# Sheet1.net
KiCad netlist of a schematic drawn in Altium Designer
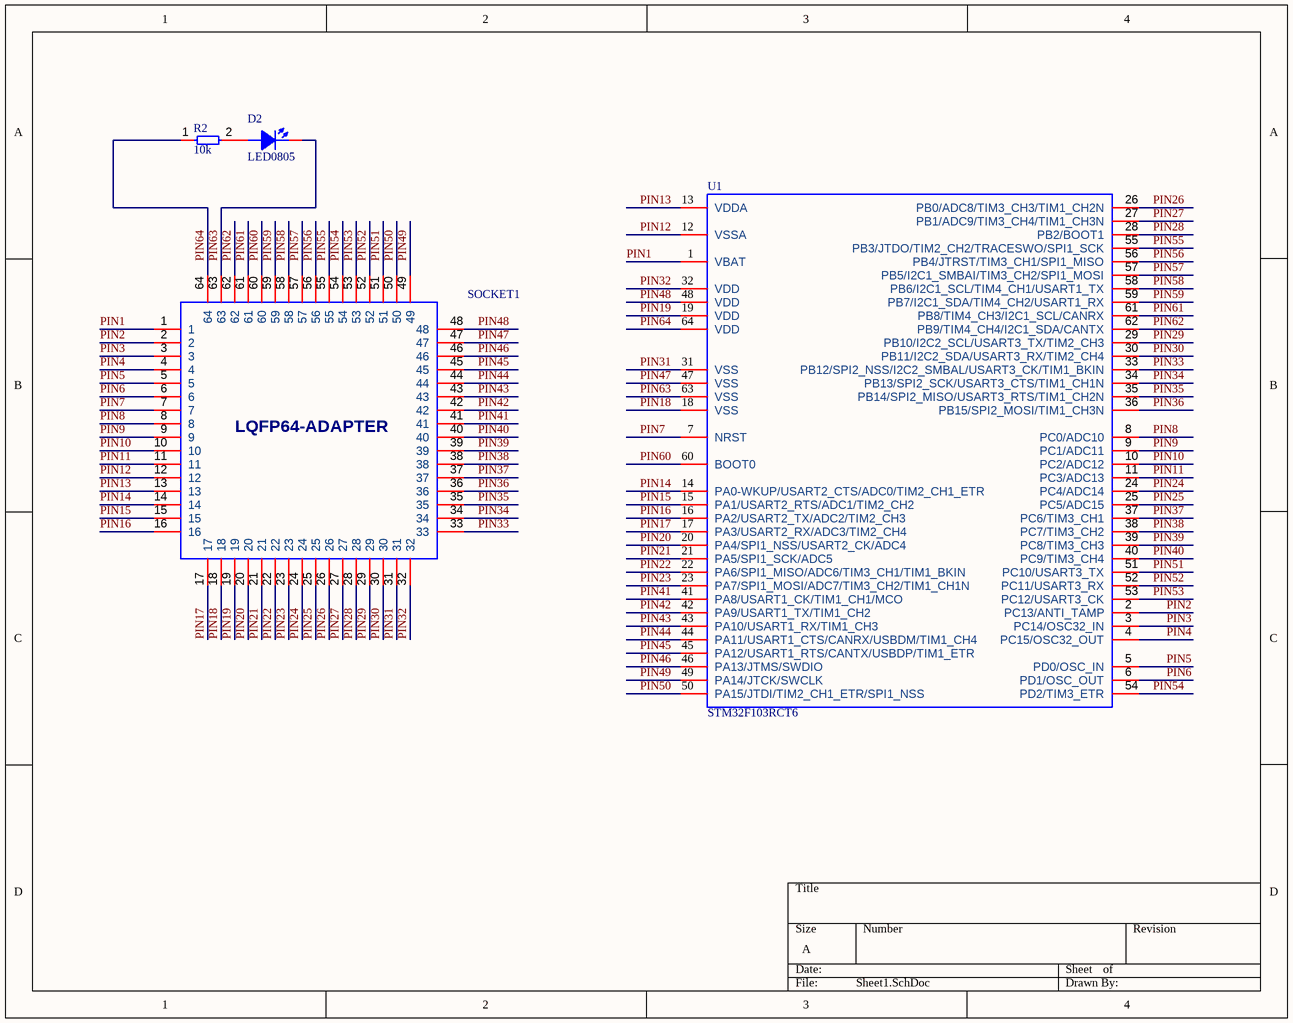
[diagram p0: Sheet1.SchDoc]

(export (version "E")
  (design (tool "Eeschema 10.0.6"))
  (components
    (comp (ref "D2") (value "LED0805") (footprint "L0805RED") (libsource (lib "SMDLibrary") (part "LED0805")))
    (comp (ref "R2") (value "10k") (footprint "R0805") (libsource (lib "SMDLibrary") (part "Resistor SMD")))
    (comp (ref "SOCKET1")
      (value "SOCKET-ADAPTER-OTQ-64-05-03")
      (footprint "SOCKET-ADAPTER-OTQ-64-05-03")
      (libsource (lib "SMDLibrary") (part "SOCKET-ADAPTER-OTQ-64-05-03"))
    )
    (comp (ref "U1")
      (value "STM32F103RCT6")
      (footprint "LQFP064_FPT-64P-M03")
      (description "LQFP64")
      (libsource (lib "SMDLibrary") (part "STM32F103RCT6"))
    )
  )
  (nets
    (net (code "1") (name "/PIN1") (class "Default")
      (node (ref "SOCKET1") (pin "1") (pinfunction "1_1") (pintype "passive"))
      (node (ref "U1") (pin "1") (pinfunction "VBAT_1") (pintype "passive"))
    )
    (net (code "2") (name "/PIN2") (class "Default")
      (node (ref "SOCKET1") (pin "2") (pinfunction "2_2") (pintype "passive"))
      (node (ref "U1") (pin "2") (pinfunction "PC13/ANTI_TAMP_2") (pintype "passive"))
    )
    (net (code "3") (name "/PIN3") (class "Default")
      (node (ref "SOCKET1") (pin "3") (pinfunction "3_3") (pintype "passive"))
      (node (ref "U1") (pin "3") (pinfunction "PC14/OSC32_IN_3") (pintype "passive"))
    )
    (net (code "4") (name "/PIN4") (class "Default")
      (node (ref "SOCKET1") (pin "4") (pinfunction "4_4") (pintype "passive"))
      (node (ref "U1") (pin "4") (pinfunction "PC15/OSC32_OUT_4") (pintype "passive"))
    )
    (net (code "5") (name "/PIN5") (class "Default")
      (node (ref "SOCKET1") (pin "5") (pinfunction "5_5") (pintype "passive"))
      (node (ref "U1") (pin "5") (pinfunction "PD0/OSC_IN_5") (pintype "passive"))
    )
    (net (code "6") (name "/PIN6") (class "Default")
      (node (ref "SOCKET1") (pin "6") (pinfunction "6_6") (pintype "passive"))
      (node (ref "U1") (pin "6") (pinfunction "PD1/OSC_OUT_6") (pintype "passive"))
    )
    (net (code "7") (name "/PIN7") (class "Default")
      (node (ref "SOCKET1") (pin "7") (pinfunction "7_7") (pintype "passive"))
      (node (ref "U1") (pin "7") (pinfunction "NRST_7") (pintype "passive"))
    )
    (net (code "8") (name "/PIN8") (class "Default")
      (node (ref "SOCKET1") (pin "8") (pinfunction "8_8") (pintype "passive"))
      (node (ref "U1") (pin "8") (pinfunction "PC0/ADC10_8") (pintype "passive"))
    )
    (net (code "9") (name "/PIN9") (class "Default")
      (node (ref "SOCKET1") (pin "9") (pinfunction "9_9") (pintype "passive"))
      (node (ref "U1") (pin "9") (pinfunction "PC1/ADC11_9") (pintype "passive"))
    )
    (net (code "10") (name "/PIN10") (class "Default")
      (node (ref "SOCKET1") (pin "10") (pinfunction "10_10") (pintype "passive"))
      (node (ref "U1") (pin "10") (pinfunction "PC2/ADC12_10") (pintype "passive"))
    )
    (net (code "11") (name "/PIN11") (class "Default")
      (node (ref "SOCKET1") (pin "11") (pinfunction "11_11") (pintype "passive"))
      (node (ref "U1") (pin "11") (pinfunction "PC3/ADC13_11") (pintype "passive"))
    )
    (net (code "12") (name "/PIN12") (class "Default")
      (node (ref "SOCKET1") (pin "12") (pinfunction "12_12") (pintype "passive"))
      (node (ref "U1") (pin "12") (pinfunction "VSSA_12") (pintype "passive"))
    )
    (net (code "13") (name "/PIN13") (class "Default")
      (node (ref "SOCKET1") (pin "13") (pinfunction "13_13") (pintype "passive"))
      (node (ref "U1") (pin "13") (pinfunction "VDDA_13") (pintype "passive"))
    )
    (net (code "14") (name "/PIN14") (class "Default")
      (node (ref "SOCKET1") (pin "14") (pinfunction "14_14") (pintype "passive"))
      (node (ref "U1") (pin "14") (pinfunction "PA0-WKUP/USART2_CTS/ADC0/TIM2_CH1_ETR_14") (pintype "passive"))
    )
    (net (code "15") (name "/PIN15") (class "Default")
      (node (ref "SOCKET1") (pin "15") (pinfunction "15_15") (pintype "passive"))
      (node (ref "U1") (pin "15") (pinfunction "PA1/USART2_RTS/ADC1/TIM2_CH2_15") (pintype "passive"))
    )
    (net (code "16") (name "/PIN16") (class "Default")
      (node (ref "SOCKET1") (pin "16") (pinfunction "16_16") (pintype "passive"))
      (node (ref "U1") (pin "16") (pinfunction "PA2/USART2_TX/ADC2/TIM2_CH3_16") (pintype "passive"))
    )
    (net (code "17") (name "/PIN17") (class "Default")
      (node (ref "SOCKET1") (pin "17") (pinfunction "17_17") (pintype "passive"))
      (node (ref "U1") (pin "17") (pinfunction "PA3/USART2_RX/ADC3/TIM2_CH4_17") (pintype "passive"))
    )
    (net (code "18") (name "/PIN18") (class "Default")
      (node (ref "SOCKET1") (pin "18") (pinfunction "18_18") (pintype "passive"))
      (node (ref "U1") (pin "18") (pinfunction "VSS_18") (pintype "passive"))
    )
    (net (code "19") (name "/PIN19") (class "Default")
      (node (ref "SOCKET1") (pin "19") (pinfunction "19_19") (pintype "passive"))
      (node (ref "U1") (pin "19") (pinfunction "VDD_19") (pintype "passive"))
    )
    (net (code "20") (name "/PIN20") (class "Default")
      (node (ref "SOCKET1") (pin "20") (pinfunction "20_20") (pintype "passive"))
      (node (ref "U1") (pin "20") (pinfunction "PA4/SPI1_NSS/USART2_CK/ADC4_20") (pintype "passive"))
    )
    (net (code "21") (name "/PIN21") (class "Default")
      (node (ref "SOCKET1") (pin "21") (pinfunction "21_21") (pintype "passive"))
      (node (ref "U1") (pin "21") (pinfunction "PA5/SPI1_SCK/ADC5_21") (pintype "passive"))
    )
    (net (code "22") (name "/PIN22") (class "Default")
      (node (ref "SOCKET1") (pin "22") (pinfunction "22_22") (pintype "passive"))
      (node (ref "U1") (pin "22") (pinfunction "PA6/SPI1_MISO/ADC6/TIM3_CH1/TIM1_BKIN_22") (pintype "passive"))
    )
    (net (code "23") (name "/PIN23") (class "Default")
      (node (ref "SOCKET1") (pin "23") (pinfunction "23_23") (pintype "passive"))
      (node (ref "U1") (pin "23") (pinfunction "PA7/SPI1_MOSI/ADC7/TIM3_CH2/TIM1_CH1N_23") (pintype "passive"))
    )
    (net (code "24") (name "/PIN24") (class "Default")
      (node (ref "SOCKET1") (pin "24") (pinfunction "24_24") (pintype "passive"))
      (node (ref "U1") (pin "24") (pinfunction "PC4/ADC14_24") (pintype "passive"))
    )
    (net (code "25") (name "/PIN25") (class "Default")
      (node (ref "SOCKET1") (pin "25") (pinfunction "25_25") (pintype "passive"))
      (node (ref "U1") (pin "25") (pinfunction "PC5/ADC15_25") (pintype "passive"))
    )
    (net (code "26") (name "/PIN26") (class "Default")
      (node (ref "SOCKET1") (pin "26") (pinfunction "26_26") (pintype "passive"))
      (node (ref "U1") (pin "26") (pinfunction "PB0/ADC8/TIM3_CH3/TIM1_CH2N_26") (pintype "passive"))
    )
    (net (code "27") (name "/PIN27") (class "Default")
      (node (ref "SOCKET1") (pin "27") (pinfunction "27_27") (pintype "passive"))
      (node (ref "U1") (pin "27") (pinfunction "PB1/ADC9/TIM3_CH4/TIM1_CH3N_27") (pintype "passive"))
    )
    (net (code "28") (name "/PIN28") (class "Default")
      (node (ref "SOCKET1") (pin "28") (pinfunction "28_28") (pintype "passive"))
      (node (ref "U1") (pin "28") (pinfunction "PB2/BOOT1_28") (pintype "passive"))
    )
    (net (code "29") (name "/PIN29") (class "Default")
      (node (ref "SOCKET1") (pin "29") (pinfunction "29_29") (pintype "passive"))
      (node (ref "U1") (pin "29") (pinfunction "PB10/I2C2_SCL/USART3_TX/TIM2_CH3_29") (pintype "passive"))
    )
    (net (code "30") (name "/PIN30") (class "Default")
      (node (ref "SOCKET1") (pin "30") (pinfunction "30_30") (pintype "passive"))
      (node (ref "U1") (pin "30") (pinfunction "PB11/I2C2_SDA/USART3_RX/TIM2_CH4_30") (pintype "passive"))
    )
    (net (code "31") (name "/PIN31") (class "Default")
      (node (ref "SOCKET1") (pin "31") (pinfunction "31_31") (pintype "passive"))
      (node (ref "U1") (pin "31") (pinfunction "VSS_31") (pintype "passive"))
    )
    (net (code "32") (name "/PIN32") (class "Default")
      (node (ref "SOCKET1") (pin "32") (pinfunction "32_32") (pintype "passive"))
      (node (ref "U1") (pin "32") (pinfunction "VDD_32") (pintype "passive"))
    )
    (net (code "33") (name "/PIN33") (class "Default")
      (node (ref "SOCKET1") (pin "33") (pinfunction "33_33") (pintype "passive"))
      (node (ref "U1") (pin "33") (pinfunction "PB12/SPI2_NSS/I2C2_SMBAL/USART3_CK/TIM1_BKIN_33") (pintype "passive"))
    )
    (net (code "34") (name "/PIN34") (class "Default")
      (node (ref "SOCKET1") (pin "34") (pinfunction "34_34") (pintype "passive"))
      (node (ref "U1") (pin "34") (pinfunction "PB13/SPI2_SCK/USART3_CTS/TIM1_CH1N_34") (pintype "passive"))
    )
    (net (code "35") (name "/PIN35") (class "Default")
      (node (ref "SOCKET1") (pin "35") (pinfunction "35_35") (pintype "passive"))
      (node (ref "U1") (pin "35") (pinfunction "PB14/SPI2_MISO/USART3_RTS/TIM1_CH2N_35") (pintype "passive"))
    )
    (net (code "36") (name "/PIN36") (class "Default")
      (node (ref "SOCKET1") (pin "36") (pinfunction "36_36") (pintype "passive"))
      (node (ref "U1") (pin "36") (pinfunction "PB15/SPI2_MOSI/TIM1_CH3N_36") (pintype "passive"))
    )
    (net (code "37") (name "/PIN37") (class "Default")
      (node (ref "SOCKET1") (pin "37") (pinfunction "37_37") (pintype "passive"))
      (node (ref "U1") (pin "37") (pinfunction "PC6/TIM3_CH1_37") (pintype "passive"))
    )
    (net (code "38") (name "/PIN38") (class "Default")
      (node (ref "SOCKET1") (pin "38") (pinfunction "38_38") (pintype "passive"))
      (node (ref "U1") (pin "38") (pinfunction "PC7/TIM3_CH2_38") (pintype "passive"))
    )
    (net (code "39") (name "/PIN39") (class "Default")
      (node (ref "SOCKET1") (pin "39") (pinfunction "39_39") (pintype "passive"))
      (node (ref "U1") (pin "39") (pinfunction "PC8/TIM3_CH3_39") (pintype "passive"))
    )
    (net (code "40") (name "/PIN40") (class "Default")
      (node (ref "SOCKET1") (pin "40") (pinfunction "40_40") (pintype "passive"))
      (node (ref "U1") (pin "40") (pinfunction "PC9/TIM3_CH4_40") (pintype "passive"))
    )
    (net (code "41") (name "/PIN41") (class "Default")
      (node (ref "SOCKET1") (pin "41") (pinfunction "41_41") (pintype "passive"))
      (node (ref "U1") (pin "41") (pinfunction "PA8/USART1_CK/TIM1_CH1/MCO_41") (pintype "passive"))
    )
    (net (code "42") (name "/PIN42") (class "Default")
      (node (ref "SOCKET1") (pin "42") (pinfunction "42_42") (pintype "passive"))
      (node (ref "U1") (pin "42") (pinfunction "PA9/USART1_TX/TIM1_CH2_42") (pintype "passive"))
    )
    (net (code "43") (name "/PIN43") (class "Default")
      (node (ref "SOCKET1") (pin "43") (pinfunction "43_43") (pintype "passive"))
      (node (ref "U1") (pin "43") (pinfunction "PA10/USART1_RX/TIM1_CH3_43") (pintype "passive"))
    )
    (net (code "44") (name "/PIN44") (class "Default")
      (node (ref "SOCKET1") (pin "44") (pinfunction "44_44") (pintype "passive"))
      (node (ref "U1") (pin "44") (pinfunction "PA11/USART1_CTS/CANRX/USBDM/TIM1_CH4_44") (pintype "passive"))
    )
    (net (code "45") (name "/PIN45") (class "Default")
      (node (ref "SOCKET1") (pin "45") (pinfunction "45_45") (pintype "passive"))
      (node (ref "U1") (pin "45") (pinfunction "PA12/USART1_RTS/CANTX/USBDP/TIM1_ETR_45") (pintype "passive"))
    )
    (net (code "46") (name "/PIN46") (class "Default")
      (node (ref "SOCKET1") (pin "46") (pinfunction "46_46") (pintype "passive"))
      (node (ref "U1") (pin "46") (pinfunction "PA13/JTMS/SWDIO_46") (pintype "passive"))
    )
    (net (code "47") (name "/PIN47") (class "Default")
      (node (ref "SOCKET1") (pin "47") (pinfunction "47_47") (pintype "passive"))
      (node (ref "U1") (pin "47") (pinfunction "VSS_47") (pintype "passive"))
    )
    (net (code "48") (name "/PIN48") (class "Default")
      (node (ref "SOCKET1") (pin "48") (pinfunction "48_48") (pintype "passive"))
      (node (ref "U1") (pin "48") (pinfunction "VDD_48") (pintype "passive"))
    )
    (net (code "49") (name "/PIN49") (class "Default")
      (node (ref "SOCKET1") (pin "49") (pinfunction "49_49") (pintype "passive"))
      (node (ref "U1") (pin "49") (pinfunction "PA14/JTCK/SWCLK_49") (pintype "passive"))
    )
    (net (code "50") (name "/PIN50") (class "Default")
      (node (ref "SOCKET1") (pin "50") (pinfunction "50_50") (pintype "passive"))
      (node (ref "U1") (pin "50") (pinfunction "PA15/JTDI/TIM2_CH1_ETR/SPI1_NSS_50") (pintype "passive"))
    )
    (net (code "51") (name "/PIN51") (class "Default")
      (node (ref "SOCKET1") (pin "51") (pinfunction "51_51") (pintype "passive"))
      (node (ref "U1") (pin "51") (pinfunction "PC10/USART3_TX_51") (pintype "passive"))
    )
    (net (code "52") (name "/PIN52") (class "Default")
      (node (ref "SOCKET1") (pin "52") (pinfunction "52_52") (pintype "passive"))
      (node (ref "U1") (pin "52") (pinfunction "PC11/USART3_RX_52") (pintype "passive"))
    )
    (net (code "53") (name "/PIN53") (class "Default")
      (node (ref "SOCKET1") (pin "53") (pinfunction "53_53") (pintype "passive"))
      (node (ref "U1") (pin "53") (pinfunction "PC12/USART3_CK_53") (pintype "passive"))
    )
    (net (code "54") (name "/PIN54") (class "Default")
      (node (ref "SOCKET1") (pin "54") (pinfunction "54_54") (pintype "passive"))
      (node (ref "U1") (pin "54") (pinfunction "PD2/TIM3_ETR_54") (pintype "passive"))
    )
    (net (code "55") (name "/PIN55") (class "Default")
      (node (ref "SOCKET1") (pin "55") (pinfunction "55_55") (pintype "passive"))
      (node (ref "U1") (pin "55") (pinfunction "PB3/JTDO/TIM2_CH2/TRACESWO/SPI1_SCK_55") (pintype "passive"))
    )
    (net (code "56") (name "/PIN56") (class "Default")
      (node (ref "SOCKET1") (pin "56") (pinfunction "56_56") (pintype "passive"))
      (node (ref "U1") (pin "56") (pinfunction "PB4/JTRST/TIM3_CH1/SPI1_MISO_56") (pintype "passive"))
    )
    (net (code "57") (name "/PIN57") (class "Default")
      (node (ref "SOCKET1") (pin "57") (pinfunction "57_57") (pintype "passive"))
      (node (ref "U1") (pin "57") (pinfunction "PB5/I2C1_SMBAI/TIM3_CH2/SPI1_MOSI_57") (pintype "passive"))
    )
    (net (code "58") (name "/PIN58") (class "Default")
      (node (ref "SOCKET1") (pin "58") (pinfunction "58_58") (pintype "passive"))
      (node (ref "U1") (pin "58") (pinfunction "PB6/I2C1_SCL/TIM4_CH1/USART1_TX_58") (pintype "passive"))
    )
    (net (code "59") (name "/PIN59") (class "Default")
      (node (ref "SOCKET1") (pin "59") (pinfunction "59_59") (pintype "passive"))
      (node (ref "U1") (pin "59") (pinfunction "PB7/I2C1_SDA/TIM4_CH2/USART1_RX_59") (pintype "passive"))
    )
    (net (code "60") (name "/PIN60") (class "Default")
      (node (ref "SOCKET1") (pin "60") (pinfunction "60_60") (pintype "passive"))
      (node (ref "U1") (pin "60") (pinfunction "BOOT0_60") (pintype "passive"))
    )
    (net (code "61") (name "/PIN61") (class "Default")
      (node (ref "SOCKET1") (pin "61") (pinfunction "61_61") (pintype "passive"))
      (node (ref "U1") (pin "61") (pinfunction "PB8/TIM4_CH3/I2C1_SCL/CANRX_61") (pintype "passive"))
    )
    (net (code "62") (name "/PIN62") (class "Default")
      (node (ref "SOCKET1") (pin "62") (pinfunction "62_62") (pintype "passive"))
      (node (ref "U1") (pin "62") (pinfunction "PB9/TIM4_CH4/I2C1_SDA/CANTX_62") (pintype "passive"))
    )
    (net (code "63") (name "/PIN63") (class "Default")
      (node (ref "D2") (pin "2") (pinfunction "K_2") (pintype "passive"))
      (node (ref "SOCKET1") (pin "63") (pinfunction "63_63") (pintype "passive"))
      (node (ref "U1") (pin "63") (pinfunction "VSS_63") (pintype "passive"))
    )
    (net (code "64") (name "/PIN64") (class "Default")
      (node (ref "R2") (pin "1") (pinfunction "1_1") (pintype "passive"))
      (node (ref "SOCKET1") (pin "64") (pinfunction "64_64") (pintype "passive"))
      (node (ref "U1") (pin "64") (pinfunction "VDD_64") (pintype "passive"))
    )
    (net (code "65") (name "Net-(D2-A)") (class "Default")
      (node (ref "D2") (pin "1") (pinfunction "A_1") (pintype "passive"))
      (node (ref "R2") (pin "2") (pinfunction "2_2") (pintype "passive"))
    )
  )
)
